# stl2-1_shield.net
KiCad netlist of a schematic drawn in EAGLE
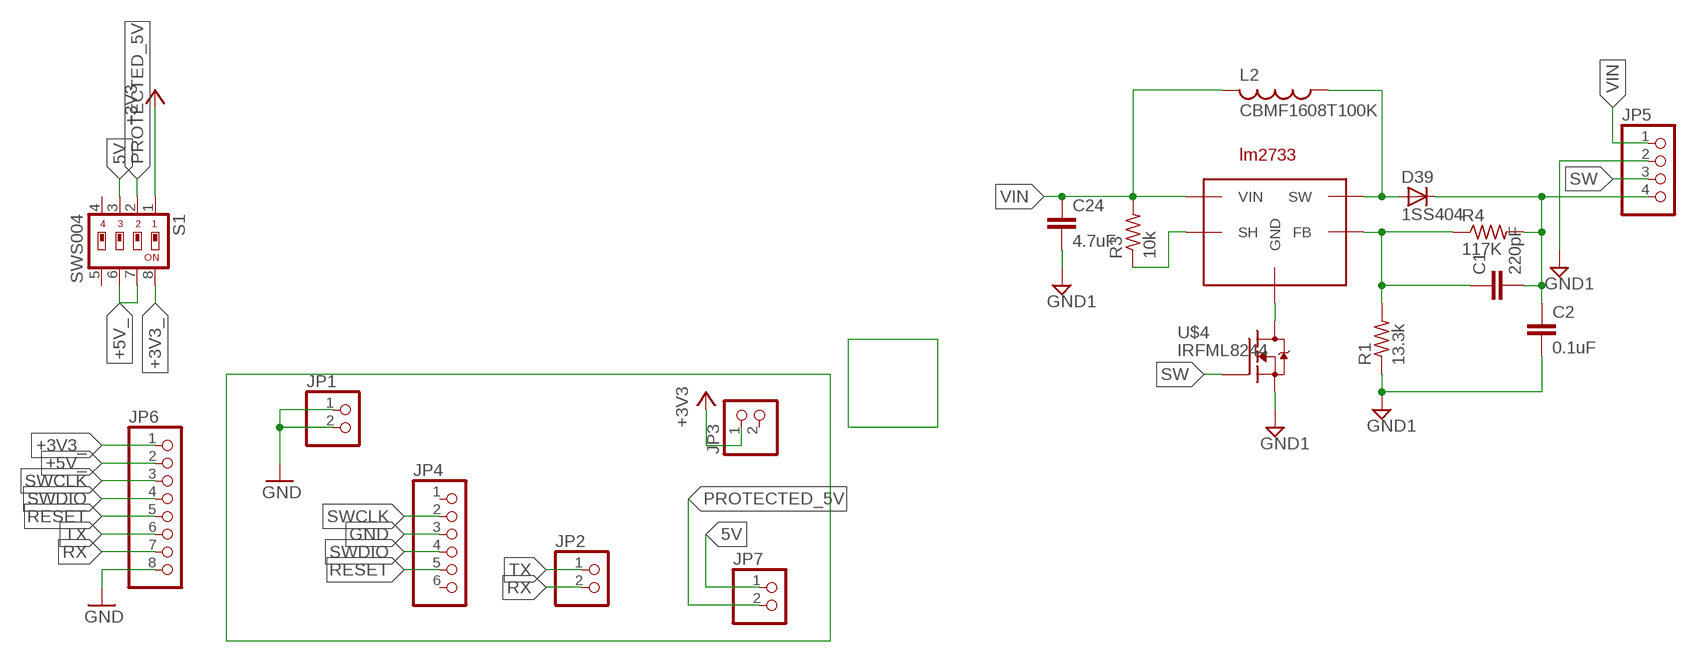
[diagram p0: schematic, sheet 1]

(export (version "E")
  (design (tool "Eeschema 10.0.6"))
  (components
    (comp (ref "C1")
      (value "220pF")
      (footprint "eagle-import:C0603K")
      (libsource (lib "eagle-import") (part "C-EUC0603K"))
    )
    (comp (ref "C2")
      (value "0.1uF")
      (footprint "eagle-import:C0603K")
      (libsource (lib "eagle-import") (part "C-EUC0603K"))
    )
    (comp (ref "C24")
      (value "4.7uF")
      (footprint "eagle-import:C0603K")
      (libsource (lib "eagle-import") (part "C-EUC0603K"))
    )
    (comp (ref "D39")
      (value "1SS404")
      (footprint "eagle-import:USC(1.25X2.5)")
      (libsource (lib "eagle-import") (part "1SS404"))
    )
    (comp (ref "JP1")
      (value "PINHD-1X2")
      (footprint "eagle-import:1X02")
      (libsource (lib "eagle-import") (part "PINHD-1X2"))
    )
    (comp (ref "JP2")
      (value "PINHD-1X2")
      (footprint "eagle-import:1X02")
      (libsource (lib "eagle-import") (part "PINHD-1X2"))
    )
    (comp (ref "JP3")
      (value "PINHD-1X2")
      (footprint "eagle-import:1X02")
      (libsource (lib "eagle-import") (part "PINHD-1X2"))
    )
    (comp (ref "JP4")
      (value "PINHD-1X6")
      (footprint "eagle-import:1X06")
      (libsource (lib "eagle-import") (part "PINHD-1X6"))
    )
    (comp (ref "JP5")
      (value "PINHD-1X4")
      (footprint "eagle-import:1X04")
      (libsource (lib "eagle-import") (part "PINHD-1X4"))
    )
    (comp (ref "JP6")
      (value "PINHD-1X8/90")
      (footprint "eagle-import:1X08_90")
      (libsource (lib "eagle-import") (part "PINHD-1X8/90"))
    )
    (comp (ref "JP7")
      (value "PINHD-1X2")
      (footprint "eagle-import:1X02")
      (libsource (lib "eagle-import") (part "PINHD-1X2"))
    )
    (comp (ref "L2")
      (value "CBMF1608T100K")
      (footprint "eagle-import:L2012C")
      (libsource (lib "eagle-import") (part "L-USL2012C"))
    )
    (comp (ref "R1")
      (value "13.3k")
      (footprint "eagle-import:R0603")
      (libsource (lib "eagle-import") (part "R-US_R0603"))
    )
    (comp (ref "R3")
      (value "10k")
      (footprint "eagle-import:R0603")
      (libsource (lib "eagle-import") (part "R-US_R0603"))
    )
    (comp (ref "R4")
      (value "117K")
      (footprint "eagle-import:R0603")
      (libsource (lib "eagle-import") (part "R-US_R0603"))
    )
    (comp (ref "S1")
      (value "SWS004")
      (footprint "eagle-import:SMS-004")
      (libsource (lib "eagle-import") (part "SWS004"))
    )
    (comp (ref "U$1")
      (value "LM2733")
      (footprint "eagle-import:SOT23-5")
      (libsource (lib "eagle-import") (part "LM2733"))
    )
    (comp (ref "U$4")
      (value "IRFML8244")
      (footprint "eagle-import:SOT23")
      (libsource (lib "eagle-import") (part "IRFML8244"))
    )
  )
  (nets
    (net (code "1") (name "+3V3") (class "Default")
      (node (ref "JP3") (pin "1") (pinfunction "1_1") (pintype "passive"))
      (node (ref "S1") (pin "1") (pinfunction "1_1") (pintype "passive"))
    )
    (net (code "2") (name "+3V3_") (class "Default")
      (node (ref "JP6") (pin "1") (pinfunction "1_1") (pintype "passive"))
      (node (ref "S1") (pin "8") (pinfunction "8_8") (pintype "passive"))
    )
    (net (code "3") (name "+5V_") (class "Default")
      (node (ref "JP6") (pin "2") (pinfunction "2_2") (pintype "passive"))
      (node (ref "S1") (pin "6") (pinfunction "6_6") (pintype "passive"))
      (node (ref "S1") (pin "7") (pinfunction "7_7") (pintype "passive"))
    )
    (net (code "4") (name "5V") (class "Default")
      (node (ref "JP7") (pin "1") (pinfunction "1_1") (pintype "passive"))
      (node (ref "S1") (pin "3") (pinfunction "3_3") (pintype "passive"))
    )
    (net (code "5") (name "GND") (class "Default")
      (node (ref "JP1") (pin "1") (pinfunction "1_1") (pintype "passive"))
      (node (ref "JP1") (pin "2") (pinfunction "2_2") (pintype "passive"))
      (node (ref "JP4") (pin "3") (pinfunction "3_3") (pintype "passive"))
      (node (ref "JP6") (pin "8") (pinfunction "8_8") (pintype "passive"))
    )
    (net (code "6") (name "GND1") (class "Default")
      (node (ref "C2") (pin "2") (pinfunction "2_2") (pintype "passive"))
      (node (ref "C24") (pin "2") (pinfunction "2_2") (pintype "passive"))
      (node (ref "JP5") (pin "2") (pinfunction "2_2") (pintype "passive"))
      (node (ref "R1") (pin "1") (pinfunction "1_1") (pintype "passive"))
      (node (ref "U$4") (pin "2") (pinfunction "S_2") (pintype "passive"))
    )
    (net (code "7") (name "Net-(C1-Pad1)") (class "Default")
      (node (ref "C1") (pin "1") (pinfunction "1_1") (pintype "passive"))
      (node (ref "R1") (pin "2") (pinfunction "2_2") (pintype "passive"))
      (node (ref "R4") (pin "1") (pinfunction "1_1") (pintype "passive"))
      (node (ref "U$1") (pin "FB") (pinfunction "FB_FB") (pintype "bidirectional"))
    )
    (net (code "8") (name "Net-(D39-C)") (class "Default")
      (node (ref "C1") (pin "2") (pinfunction "2_2") (pintype "passive"))
      (node (ref "C2") (pin "1") (pinfunction "1_1") (pintype "passive"))
      (node (ref "D39") (pin "K") (pinfunction "C_K") (pintype "passive"))
      (node (ref "JP5") (pin "4") (pinfunction "4_4") (pintype "passive"))
      (node (ref "R4") (pin "2") (pinfunction "2_2") (pintype "passive"))
    )
    (net (code "9") (name "Net-(D39-PadA)") (class "Default")
      (node (ref "D39") (pin "A") (pinfunction "A_A") (pintype "passive"))
      (node (ref "L2") (pin "1") (pinfunction "1_1") (pintype "passive"))
      (node (ref "U$1") (pin "SW") (pinfunction "SW_SW") (pintype "bidirectional"))
    )
    (net (code "10") (name "Net-(R3-Pad1)") (class "Default")
      (node (ref "R3") (pin "1") (pinfunction "1_1") (pintype "passive"))
      (node (ref "U$1") (pin "SH") (pinfunction "SH_SH") (pintype "bidirectional"))
    )
    (net (code "11") (name "Net-(U$4-D)") (class "Default")
      (node (ref "U$1") (pin "GND") (pinfunction "GND_GND") (pintype "bidirectional"))
      (node (ref "U$4") (pin "3") (pinfunction "D_3") (pintype "passive"))
    )
    (net (code "12") (name "PROTECTED_5V") (class "Default")
      (node (ref "JP7") (pin "2") (pinfunction "2_2") (pintype "passive"))
      (node (ref "S1") (pin "2") (pinfunction "2_2") (pintype "passive"))
    )
    (net (code "13") (name "RESET") (class "Default")
      (node (ref "JP4") (pin "5") (pinfunction "5_5") (pintype "passive"))
      (node (ref "JP6") (pin "5") (pinfunction "5_5") (pintype "passive"))
    )
    (net (code "14") (name "RX") (class "Default")
      (node (ref "JP2") (pin "2") (pinfunction "2_2") (pintype "passive"))
      (node (ref "JP6") (pin "7") (pinfunction "7_7") (pintype "passive"))
    )
    (net (code "15") (name "SW") (class "Default")
      (node (ref "JP5") (pin "3") (pinfunction "3_3") (pintype "passive"))
      (node (ref "U$4") (pin "1") (pinfunction "G_1") (pintype "passive"))
    )
    (net (code "16") (name "SWCLK") (class "Default")
      (node (ref "JP4") (pin "2") (pinfunction "2_2") (pintype "passive"))
      (node (ref "JP6") (pin "3") (pinfunction "3_3") (pintype "passive"))
    )
    (net (code "17") (name "SWDIO") (class "Default")
      (node (ref "JP4") (pin "4") (pinfunction "4_4") (pintype "passive"))
      (node (ref "JP6") (pin "4") (pinfunction "4_4") (pintype "passive"))
    )
    (net (code "18") (name "TX") (class "Default")
      (node (ref "JP2") (pin "1") (pinfunction "1_1") (pintype "passive"))
      (node (ref "JP6") (pin "6") (pinfunction "6_6") (pintype "passive"))
    )
    (net (code "19") (name "VIN") (class "Default")
      (node (ref "C24") (pin "1") (pinfunction "1_1") (pintype "passive"))
      (node (ref "JP5") (pin "1") (pinfunction "1_1") (pintype "passive"))
      (node (ref "L2") (pin "2") (pinfunction "2_2") (pintype "passive"))
      (node (ref "R3") (pin "2") (pinfunction "2_2") (pintype "passive"))
      (node (ref "U$1") (pin "VIN") (pinfunction "VIN_VIN") (pintype "bidirectional"))
    )
    (net (code "20") (name "unconnected-(JP3-Pad2)") (class "Default")
      (node (ref "JP3") (pin "2") (pinfunction "2_2") (pintype "passive"))
    )
    (net (code "21") (name "unconnected-(JP4-Pad1)") (class "Default")
      (node (ref "JP4") (pin "1") (pinfunction "1_1") (pintype "passive"))
    )
    (net (code "22") (name "unconnected-(JP4-Pad6)") (class "Default")
      (node (ref "JP4") (pin "6") (pinfunction "6_6") (pintype "passive"))
    )
    (net (code "23") (name "unconnected-(S1-Pad4)") (class "Default")
      (node (ref "S1") (pin "4") (pinfunction "4_4") (pintype "passive"))
    )
    (net (code "24") (name "unconnected-(S1-Pad5)") (class "Default")
      (node (ref "S1") (pin "5") (pinfunction "5_5") (pintype "passive"))
    )
  )
)
